# ESP32.net
KiCad netlist of a schematic drawn in Altium Designer
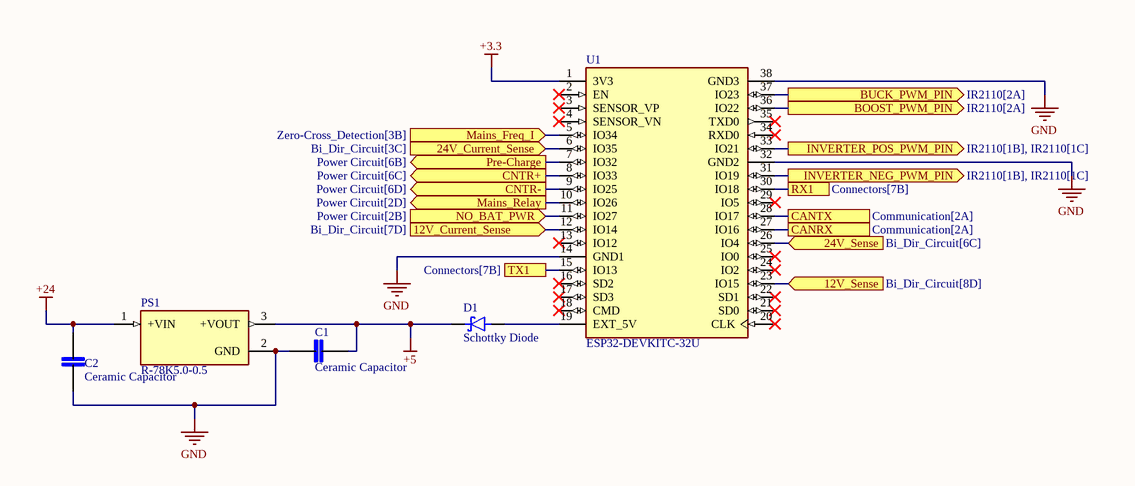
[diagram p0: ESP32.SchDoc]

(export (version "E")
  (design (tool "Eeschema 10.0.6"))
  (components
    (comp (ref "C1")
      (value "Ceramic Capacitor")
      (footprint "Ceramic Capacitor")
      (fields (field (name "MP") "LD051A121KAB2A") (field (name "MF") "AVX"))
      (libsource (lib "") (part "Ceramic Capacitor_1"))
    )
    (comp (ref "C2")
      (value "Ceramic Capacitor")
      (footprint "Ceramic Capacitor")
      (fields (field (name "MP") "LD051A121KAB2A") (field (name "MF") "AVX"))
      (libsource (lib "Capacitors Through Hole") (part "Ceramic Capacitor"))
    )
    (comp (ref "D1")
      (value "Schottky Diode")
      (footprint "Common Trhough Hole")
      (fields (field (name "MF") "Diodes Inc.") (field (name "MP") "1N5817-T"))
      (libsource (lib "Diodes Through Hole") (part "Schottky Diode"))
    )
    (comp (ref "PS1")
      (value "R-78K5.0-0.5")
      (footprint "CONV_R-78K5.0-0.5")
      (description "0.5A DC/DC-Converter 'INNOLINE' SIP3 reg")
      (fields (field (name "MF") "Recom Power"))
      (libsource (lib "Voltage Regulators Through Hole") (part "R-78K5.0-0.5"))
    )
    (comp (ref "U1")
      (value "ESP32-DEVKITC-32U")
      (footprint "MODULE_ESP32-DEVKITC-32U")
      (fields (field (name "MF") "Espressif Systems"))
      (libsource (lib "MySCH_Library") (part "ESP32-DEVKITC-32U"))
    )
  )
  (nets
    (net (code "1") (name "+3.3") (class "Default")
      (node (ref "U1") (pin "1") (pinfunction "3V3_1") (pintype "power_in"))
    )
    (net (code "2") (name "+5") (class "Default")
      (node (ref "C1") (pin "2") (pinfunction "2_2") (pintype "passive"))
      (node (ref "D1") (pin "1") (pinfunction "K_1") (pintype "passive"))
      (node (ref "PS1") (pin "3") (pinfunction "+VOUT_3") (pintype "output"))
    )
    (net (code "3") (name "+24") (class "Default")
      (node (ref "C2") (pin "2") (pinfunction "2_2") (pintype "passive"))
      (node (ref "PS1") (pin "1") (pinfunction "+VIN_1") (pintype "input"))
    )
    (net (code "4") (name "/12V_Current_Sense") (class "Default")
      (node (ref "U1") (pin "12") (pinfunction "IO14_12") (pintype "bidirectional"))
    )
    (net (code "5") (name "/12V_Sense") (class "Default")
      (node (ref "U1") (pin "23") (pinfunction "IO15_23") (pintype "bidirectional"))
    )
    (net (code "6") (name "/24V_Current_Sense") (class "Default")
      (node (ref "U1") (pin "6") (pinfunction "IO35_6") (pintype "bidirectional"))
    )
    (net (code "7") (name "/24V_Sense") (class "Default")
      (node (ref "U1") (pin "26") (pinfunction "IO4_26") (pintype "bidirectional"))
    )
    (net (code "8") (name "/BOOST_PWM_PIN") (class "Default")
      (node (ref "U1") (pin "36") (pinfunction "IO22_36") (pintype "bidirectional"))
    )
    (net (code "9") (name "/BUCK_PWM_PIN") (class "Default")
      (node (ref "U1") (pin "37") (pinfunction "IO23_37") (pintype "bidirectional"))
    )
    (net (code "10") (name "/CANRX") (class "Default")
      (node (ref "U1") (pin "27") (pinfunction "IO16_27") (pintype "bidirectional"))
    )
    (net (code "11") (name "/CANTX") (class "Default")
      (node (ref "U1") (pin "28") (pinfunction "IO17_28") (pintype "bidirectional"))
    )
    (net (code "12") (name "/CNTR+") (class "Default")
      (node (ref "U1") (pin "8") (pinfunction "IO33_8") (pintype "bidirectional"))
    )
    (net (code "13") (name "/CNTR-") (class "Default")
      (node (ref "U1") (pin "9") (pinfunction "IO25_9") (pintype "bidirectional"))
    )
    (net (code "14") (name "/INVERTER_NEG_PWM_PIN") (class "Default")
      (node (ref "U1") (pin "31") (pinfunction "IO19_31") (pintype "bidirectional"))
    )
    (net (code "15") (name "/INVERTER_POS_PWM_PIN") (class "Default")
      (node (ref "U1") (pin "33") (pinfunction "IO21_33") (pintype "bidirectional"))
    )
    (net (code "16") (name "/Mains_Freq_I") (class "Default")
      (node (ref "U1") (pin "5") (pinfunction "IO34_5") (pintype "bidirectional"))
    )
    (net (code "17") (name "/Mains_Relay") (class "Default")
      (node (ref "U1") (pin "10") (pinfunction "IO26_10") (pintype "bidirectional"))
    )
    (net (code "18") (name "/NO_BAT_PWR") (class "Default")
      (node (ref "U1") (pin "11") (pinfunction "IO27_11") (pintype "bidirectional"))
    )
    (net (code "19") (name "/Pre-Charge") (class "Default")
      (node (ref "U1") (pin "7") (pinfunction "IO32_7") (pintype "bidirectional"))
    )
    (net (code "20") (name "/RX1") (class "Default")
      (node (ref "U1") (pin "30") (pinfunction "IO18_30") (pintype "bidirectional"))
    )
    (net (code "21") (name "/TX1") (class "Default")
      (node (ref "U1") (pin "15") (pinfunction "IO13_15") (pintype "bidirectional"))
    )
    (net (code "22") (name "GND") (class "Default")
      (node (ref "C1") (pin "1") (pinfunction "1_1") (pintype "passive"))
      (node (ref "C2") (pin "1") (pinfunction "1_1") (pintype "passive"))
      (node (ref "PS1") (pin "2") (pinfunction "GND_2") (pintype "power_in"))
      (node (ref "U1") (pin "14") (pinfunction "GND1_14") (pintype "power_in"))
      (node (ref "U1") (pin "32") (pinfunction "GND2_32") (pintype "power_in"))
      (node (ref "U1") (pin "38") (pinfunction "GND3_38") (pintype "power_in"))
    )
    (net (code "23") (name "Net-(D1-A)") (class "Default")
      (node (ref "D1") (pin "2") (pinfunction "A_2") (pintype "passive"))
      (node (ref "U1") (pin "19") (pinfunction "EXT_5V_19") (pintype "power_in"))
    )
    (net (code "24") (name "unconnected-(U1-CLK-Pad20)") (class "Default")
      (node (ref "U1") (pin "20") (pinfunction "CLK_20") (pintype "input+no_connect"))
    )
    (net (code "25") (name "unconnected-(U1-CMD-Pad18)") (class "Default")
      (node (ref "U1") (pin "18") (pinfunction "CMD_18") (pintype "bidirectional+no_connect"))
    )
    (net (code "26") (name "unconnected-(U1-EN-Pad2)") (class "Default")
      (node (ref "U1") (pin "2") (pinfunction "EN_2") (pintype "input+no_connect"))
    )
    (net (code "27") (name "unconnected-(U1-IO0-Pad25)") (class "Default")
      (node (ref "U1") (pin "25") (pinfunction "IO0_25") (pintype "bidirectional+no_connect"))
    )
    (net (code "28") (name "unconnected-(U1-IO2-Pad24)") (class "Default")
      (node (ref "U1") (pin "24") (pinfunction "IO2_24") (pintype "bidirectional+no_connect"))
    )
    (net (code "29") (name "unconnected-(U1-IO5-Pad29)") (class "Default")
      (node (ref "U1") (pin "29") (pinfunction "IO5_29") (pintype "bidirectional+no_connect"))
    )
    (net (code "30") (name "unconnected-(U1-IO12-Pad13)") (class "Default")
      (node (ref "U1") (pin "13") (pinfunction "IO12_13") (pintype "bidirectional+no_connect"))
    )
    (net (code "31") (name "unconnected-(U1-RXD0-Pad34)") (class "Default")
      (node (ref "U1") (pin "34") (pinfunction "RXD0_34") (pintype "input+no_connect"))
    )
    (net (code "32") (name "unconnected-(U1-SD0-Pad21)") (class "Default")
      (node (ref "U1") (pin "21") (pinfunction "SD0_21") (pintype "bidirectional+no_connect"))
    )
    (net (code "33") (name "unconnected-(U1-SD1-Pad22)") (class "Default")
      (node (ref "U1") (pin "22") (pinfunction "SD1_22") (pintype "bidirectional+no_connect"))
    )
    (net (code "34") (name "unconnected-(U1-SD2-Pad16)") (class "Default")
      (node (ref "U1") (pin "16") (pinfunction "SD2_16") (pintype "bidirectional+no_connect"))
    )
    (net (code "35") (name "unconnected-(U1-SD3-Pad17)") (class "Default")
      (node (ref "U1") (pin "17") (pinfunction "SD3_17") (pintype "bidirectional+no_connect"))
    )
    (net (code "36") (name "unconnected-(U1-SENSOR_VN-Pad4)") (class "Default")
      (node (ref "U1") (pin "4") (pinfunction "SENSOR_VN_4") (pintype "input+no_connect"))
    )
    (net (code "37") (name "unconnected-(U1-SENSOR_VP-Pad3)") (class "Default")
      (node (ref "U1") (pin "3") (pinfunction "SENSOR_VP_3") (pintype "input+no_connect"))
    )
    (net (code "38") (name "unconnected-(U1-TXD0-Pad35)") (class "Default")
      (node (ref "U1") (pin "35") (pinfunction "TXD0_35") (pintype "output+no_connect"))
    )
  )
)
